# Shield_Schematic.net
KiCad netlist of a schematic drawn in EAGLE
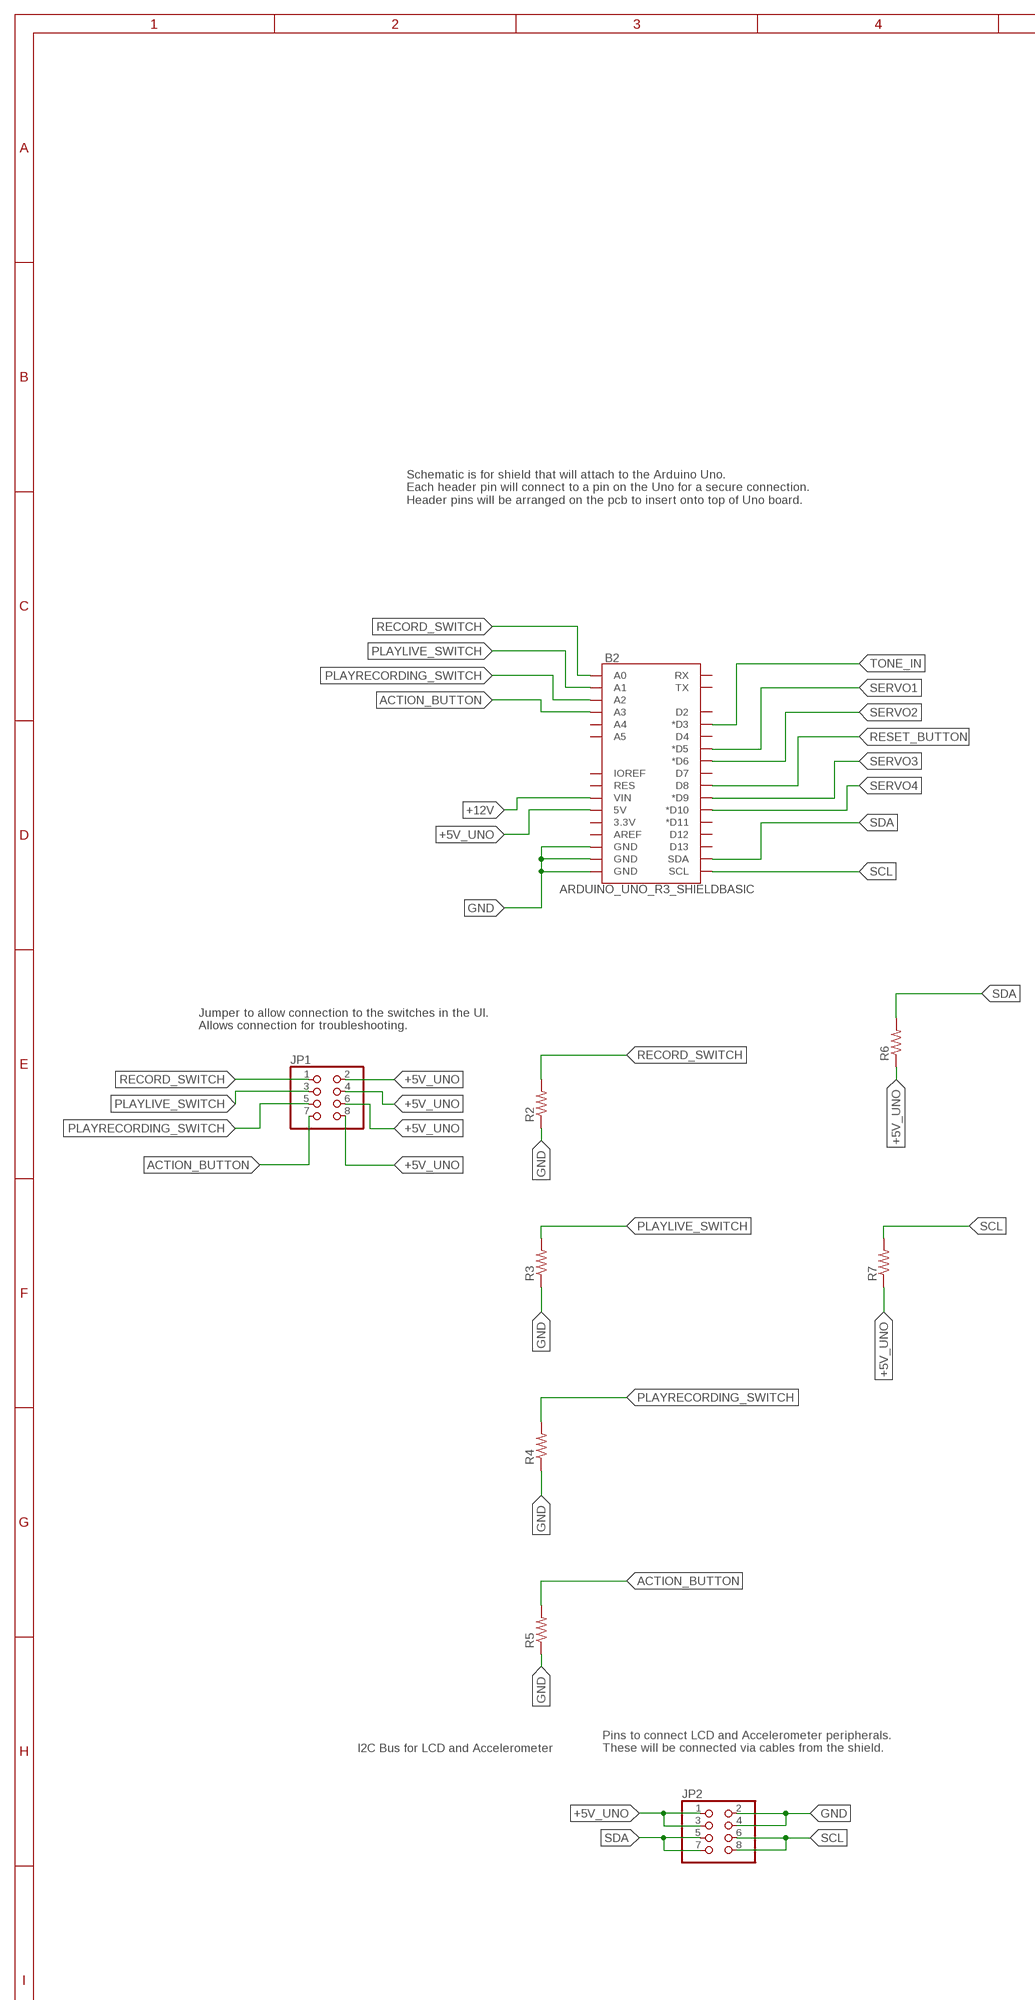
[diagram p0: schematic, sheet 1, part 1 of 2]
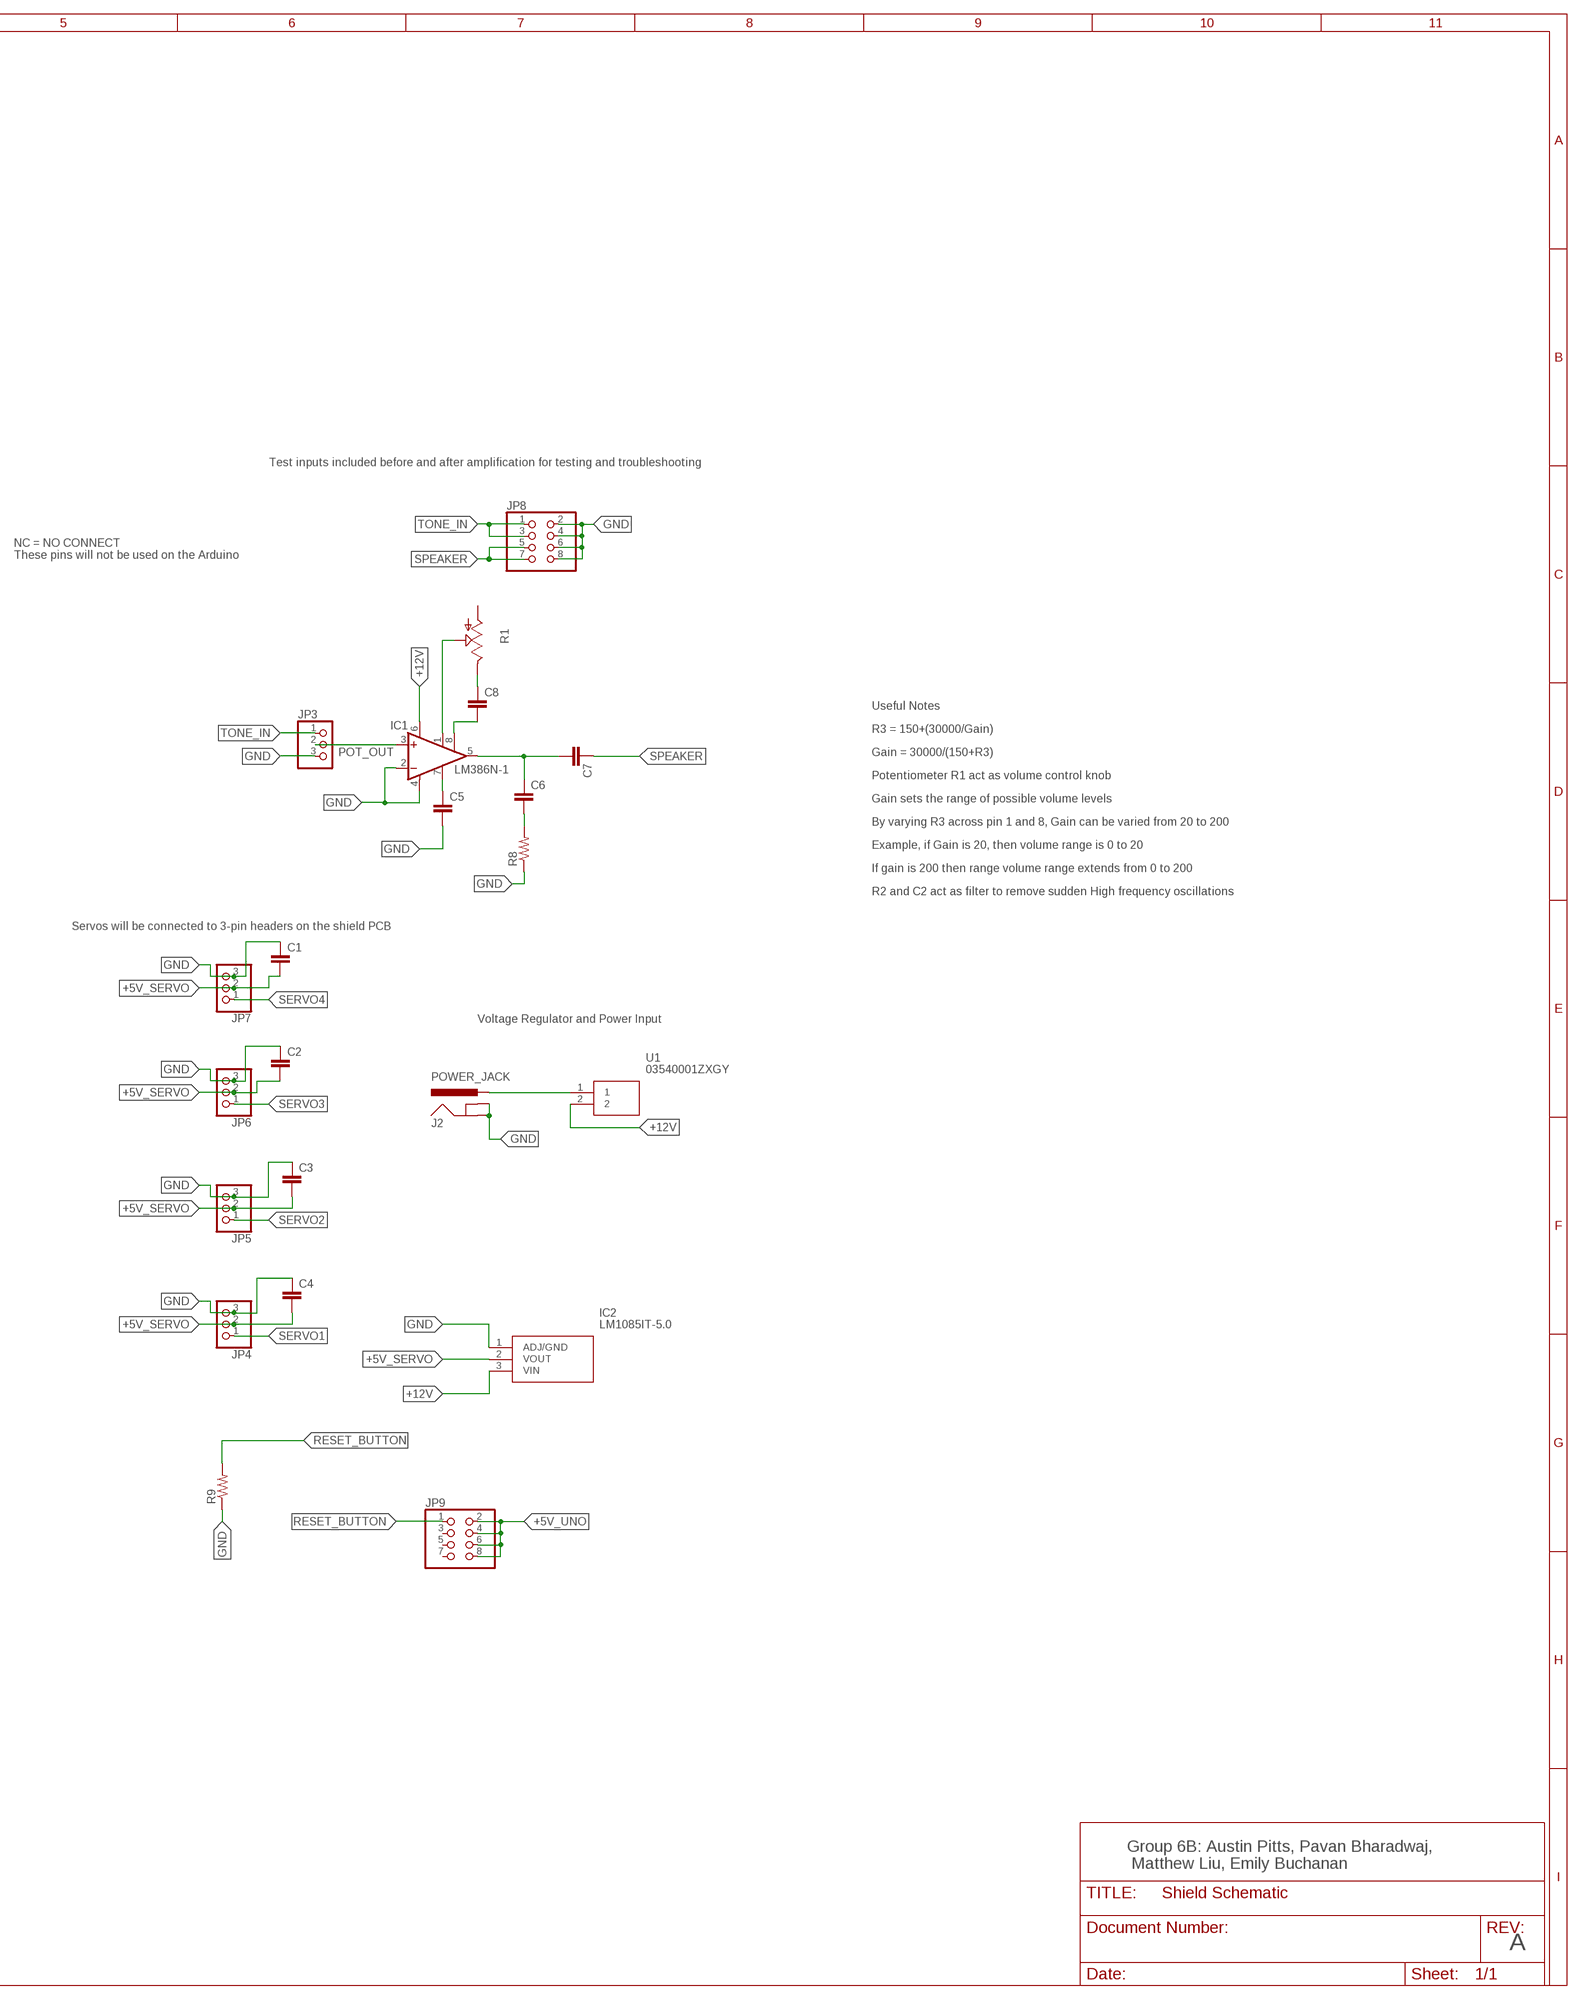
[diagram p1: schematic, sheet 1, part 2 of 2]

(export (version "E")
  (design (tool "Eeschema 10.0.6"))
  (components
    (comp (ref "B2")
      (value "ARDUINO_UNO_R3_SHIELDBASIC")
      (footprint "eagle-import:UNO_R3_SHIELD")
      (libsource (lib "eagle-import") (part "ARDUINO_UNO_R3_SHIELDBASIC"))
    )
    (comp (ref "C1")
      (value "C2,5-3")
      (footprint "eagle-import:C2.5-3")
      (libsource (lib "eagle-import") (part "C2,5-3"))
    )
    (comp (ref "C2")
      (value "C2,5-3")
      (footprint "eagle-import:C2.5-3")
      (libsource (lib "eagle-import") (part "C2,5-3"))
    )
    (comp (ref "C3")
      (value "C2,5-3")
      (footprint "eagle-import:C2.5-3")
      (libsource (lib "eagle-import") (part "C2,5-3"))
    )
    (comp (ref "C4")
      (value "C2,5-3")
      (footprint "eagle-import:C2.5-3")
      (libsource (lib "eagle-import") (part "C2,5-3"))
    )
    (comp (ref "C5")
      (value "C2,5-3")
      (footprint "eagle-import:C2.5-3")
      (libsource (lib "eagle-import") (part "C2,5-3"))
    )
    (comp (ref "C6")
      (value "C2,5-3")
      (footprint "eagle-import:C2.5-3")
      (libsource (lib "eagle-import") (part "C2,5-3"))
    )
    (comp (ref "C7")
      (value "C2,5-3")
      (footprint "eagle-import:C2.5-3")
      (libsource (lib "eagle-import") (part "C2,5-3"))
    )
    (comp (ref "C8")
      (value "C2,5-3")
      (footprint "eagle-import:C2.5-3")
      (libsource (lib "eagle-import") (part "C2,5-3"))
    )
    (comp (ref "IC1")
      (value "LM386N-1")
      (footprint "eagle-import:DIL08")
      (libsource (lib "eagle-import") (part "LM386?-N1"))
    )
    (comp (ref "IC2")
      (value "LM1085IT-5.0")
      (footprint "eagle-import:TO254P470X1016X2222-3P")
      (fields (field (name "MOUSER_PART_NUMBER") "926-LM1085IT-50"))
      (libsource (lib "eagle-import") (part "LM1085IT-5.0"))
    )
    (comp (ref "J2")
      (value "POWER_JACK")
      (footprint "eagle-import:POWER_JACK_PTH")
      (libsource (lib "eagle-import") (part "POWER_JACK"))
    )
    (comp (ref "JP1")
      (value "PINHD-2X4")
      (footprint "eagle-import:2X04")
      (libsource (lib "eagle-import") (part "PINHD-2X4"))
    )
    (comp (ref "JP2")
      (value "PINHD-2X4")
      (footprint "eagle-import:2X04")
      (libsource (lib "eagle-import") (part "PINHD-2X4"))
    )
    (comp (ref "JP3")
      (value "PINHD-1X3")
      (footprint "eagle-import:1X03")
      (libsource (lib "eagle-import") (part "PINHD-1X3"))
    )
    (comp (ref "JP4")
      (value "PINHD-1X3")
      (footprint "eagle-import:1X03")
      (libsource (lib "eagle-import") (part "adafruit_420_PINHD-1X3"))
    )
    (comp (ref "JP5")
      (value "PINHD-1X3")
      (footprint "eagle-import:1X03")
      (libsource (lib "eagle-import") (part "adafruit_420_PINHD-1X3"))
    )
    (comp (ref "JP6")
      (value "PINHD-1X3")
      (footprint "eagle-import:1X03")
      (libsource (lib "eagle-import") (part "adafruit_420_PINHD-1X3"))
    )
    (comp (ref "JP7")
      (value "PINHD-1X3")
      (footprint "eagle-import:1X03")
      (libsource (lib "eagle-import") (part "adafruit_420_PINHD-1X3"))
    )
    (comp (ref "JP8")
      (value "PINHD-2X4")
      (footprint "eagle-import:2X04")
      (libsource (lib "eagle-import") (part "PINHD-2X4"))
    )
    (comp (ref "JP9")
      (value "PINHD-2X4")
      (footprint "eagle-import:2X04")
      (libsource (lib "eagle-import") (part "PINHD-2X4"))
    )
    (comp (ref "R1")
      (value "TRIM_US-B25P")
      (footprint "eagle-import:B25P")
      (libsource (lib "eagle-import") (part "TRIM_US-B25P"))
    )
    (comp (ref "R2")
      (value "R-US_0207/7")
      (footprint "eagle-import:0207_7")
      (libsource (lib "eagle-import") (part "R-US_0207/7"))
    )
    (comp (ref "R3")
      (value "R-US_0207/7")
      (footprint "eagle-import:0207_7")
      (libsource (lib "eagle-import") (part "R-US_0207/7"))
    )
    (comp (ref "R4")
      (value "R-US_0207/7")
      (footprint "eagle-import:0207_7")
      (libsource (lib "eagle-import") (part "R-US_0207/7"))
    )
    (comp (ref "R5")
      (value "R-US_0207/7")
      (footprint "eagle-import:0207_7")
      (libsource (lib "eagle-import") (part "R-US_0207/7"))
    )
    (comp (ref "R6")
      (value "R-US_0207/7")
      (footprint "eagle-import:0207_7")
      (libsource (lib "eagle-import") (part "R-US_0207/7"))
    )
    (comp (ref "R7")
      (value "R-US_0207/7")
      (footprint "eagle-import:0207_7")
      (libsource (lib "eagle-import") (part "R-US_0207/7"))
    )
    (comp (ref "R8")
      (value "R-US_0207/7")
      (footprint "eagle-import:0207_7")
      (libsource (lib "eagle-import") (part "R-US_0207/7"))
    )
    (comp (ref "R9")
      (value "R-US_0207/7")
      (footprint "eagle-import:0207_7")
      (libsource (lib "eagle-import") (part "R-US_0207/7"))
    )
    (comp (ref "U1")
      (value "03540001ZXGY")
      (footprint "eagle-import:03540101ZXGY")
      (fields (field (name "MOUSER_PART_NUMBER") "576-03540001ZXGY"))
      (libsource (lib "eagle-import") (part "03540001ZXGY"))
    )
  )
  (nets
    (net (code "1") (name "+5V_SERVO") (class "Default")
      (node (ref "C1") (pin "2") (pinfunction "2_2") (pintype "passive"))
      (node (ref "C2") (pin "2") (pinfunction "2_2") (pintype "passive"))
      (node (ref "C3") (pin "2") (pinfunction "2_2") (pintype "passive"))
      (node (ref "C4") (pin "2") (pinfunction "2_2") (pintype "passive"))
      (node (ref "IC2") (pin "2") (pinfunction "VOUT_2") (pintype "bidirectional"))
      (node (ref "JP4") (pin "2") (pinfunction "2_2") (pintype "passive"))
      (node (ref "JP5") (pin "2") (pinfunction "2_2") (pintype "passive"))
      (node (ref "JP6") (pin "2") (pinfunction "2_2") (pintype "passive"))
      (node (ref "JP7") (pin "2") (pinfunction "2_2") (pintype "passive"))
    )
    (net (code "2") (name "+5V_UNO") (class "Default")
      (node (ref "B2") (pin "5V") (pinfunction "5V_5V") (pintype "bidirectional"))
      (node (ref "JP1") (pin "2") (pinfunction "2_2") (pintype "passive"))
      (node (ref "JP1") (pin "4") (pinfunction "4_4") (pintype "passive"))
      (node (ref "JP1") (pin "6") (pinfunction "6_6") (pintype "passive"))
      (node (ref "JP1") (pin "8") (pinfunction "8_8") (pintype "passive"))
      (node (ref "JP2") (pin "1") (pinfunction "1_1") (pintype "passive"))
      (node (ref "JP2") (pin "3") (pinfunction "3_3") (pintype "passive"))
      (node (ref "JP9") (pin "2") (pinfunction "2_2") (pintype "passive"))
      (node (ref "JP9") (pin "4") (pinfunction "4_4") (pintype "passive"))
      (node (ref "JP9") (pin "6") (pinfunction "6_6") (pintype "passive"))
      (node (ref "JP9") (pin "8") (pinfunction "8_8") (pintype "passive"))
      (node (ref "R6") (pin "1") (pinfunction "1_1") (pintype "passive"))
      (node (ref "R7") (pin "1") (pinfunction "1_1") (pintype "passive"))
    )
    (net (code "3") (name "+12V") (class "Default")
      (node (ref "B2") (pin "VIN") (pinfunction "VIN_VIN") (pintype "bidirectional"))
      (node (ref "IC1") (pin "6") (pinfunction "VS_6") (pintype "power_in"))
      (node (ref "IC2") (pin "3") (pinfunction "VIN_3") (pintype "bidirectional"))
      (node (ref "U1") (pin "2") (pinfunction "2_2") (pintype "bidirectional"))
    )
    (net (code "4") (name "/POT_OUT") (class "Default")
      (node (ref "IC1") (pin "3") (pinfunction "+IN_3") (pintype "input"))
      (node (ref "JP3") (pin "2") (pinfunction "2_2") (pintype "passive"))
    )
    (net (code "5") (name "ACTION_BUTTON") (class "Default")
      (node (ref "B2") (pin "A3") (pinfunction "A3_A3") (pintype "bidirectional"))
      (node (ref "JP1") (pin "7") (pinfunction "7_7") (pintype "passive"))
      (node (ref "R5") (pin "2") (pinfunction "2_2") (pintype "passive"))
    )
    (net (code "6") (name "GND") (class "Default")
      (node (ref "B2") (pin "GND@0") (pinfunction "GND_GND@0") (pintype "bidirectional"))
      (node (ref "B2") (pin "GND@1") (pinfunction "GND_GND@1") (pintype "bidirectional"))
      (node (ref "B2") (pin "GND@2") (pinfunction "GND_GND@2") (pintype "bidirectional"))
      (node (ref "C1") (pin "1") (pinfunction "1_1") (pintype "passive"))
      (node (ref "C2") (pin "1") (pinfunction "1_1") (pintype "passive"))
      (node (ref "C3") (pin "1") (pinfunction "1_1") (pintype "passive"))
      (node (ref "C4") (pin "1") (pinfunction "1_1") (pintype "passive"))
      (node (ref "C5") (pin "2") (pinfunction "2_2") (pintype "passive"))
      (node (ref "IC1") (pin "2") (pinfunction "-IN_2") (pintype "input"))
      (node (ref "IC1") (pin "4") (pinfunction "GND_4") (pintype "power_in"))
      (node (ref "IC2") (pin "1") (pinfunction "ADJ/GND_1") (pintype "bidirectional"))
      (node (ref "J2") (pin "GND") (pinfunction "GND_GND") (pintype "bidirectional"))
      (node (ref "J2") (pin "GNDBREAK") (pinfunction "GNDBREAK_GNDBREAK") (pintype "bidirectional"))
      (node (ref "JP2") (pin "2") (pinfunction "2_2") (pintype "passive"))
      (node (ref "JP2") (pin "4") (pinfunction "4_4") (pintype "passive"))
      (node (ref "JP3") (pin "3") (pinfunction "3_3") (pintype "passive"))
      (node (ref "JP4") (pin "3") (pinfunction "3_3") (pintype "passive"))
      (node (ref "JP5") (pin "3") (pinfunction "3_3") (pintype "passive"))
      (node (ref "JP6") (pin "3") (pinfunction "3_3") (pintype "passive"))
      (node (ref "JP7") (pin "3") (pinfunction "3_3") (pintype "passive"))
      (node (ref "JP8") (pin "2") (pinfunction "2_2") (pintype "passive"))
      (node (ref "JP8") (pin "4") (pinfunction "4_4") (pintype "passive"))
      (node (ref "JP8") (pin "6") (pinfunction "6_6") (pintype "passive"))
      (node (ref "JP8") (pin "8") (pinfunction "8_8") (pintype "passive"))
      (node (ref "R2") (pin "1") (pinfunction "1_1") (pintype "passive"))
      (node (ref "R3") (pin "1") (pinfunction "1_1") (pintype "passive"))
      (node (ref "R4") (pin "1") (pinfunction "1_1") (pintype "passive"))
      (node (ref "R5") (pin "1") (pinfunction "1_1") (pintype "passive"))
      (node (ref "R8") (pin "1") (pinfunction "1_1") (pintype "passive"))
      (node (ref "R9") (pin "1") (pinfunction "1_1") (pintype "passive"))
    )
    (net (code "7") (name "Net-(C6-Pad2)") (class "Default")
      (node (ref "C6") (pin "2") (pinfunction "2_2") (pintype "passive"))
      (node (ref "R8") (pin "2") (pinfunction "2_2") (pintype "passive"))
    )
    (net (code "8") (name "Net-(C8-Pad1)") (class "Default")
      (node (ref "C8") (pin "1") (pinfunction "1_1") (pintype "passive"))
      (node (ref "R1") (pin "E") (pinfunction "E_E") (pintype "passive"))
    )
    (net (code "9") (name "Net-(C8-Pad2)") (class "Default")
      (node (ref "C8") (pin "2") (pinfunction "2_2") (pintype "passive"))
      (node (ref "IC1") (pin "8") (pinfunction "GAIN_8") (pintype "passive"))
    )
    (net (code "10") (name "Net-(IC1-BYPASS)") (class "Default")
      (node (ref "C5") (pin "1") (pinfunction "1_1") (pintype "passive"))
      (node (ref "IC1") (pin "7") (pinfunction "BYPASS_7") (pintype "passive"))
    )
    (net (code "11") (name "Net-(IC1-GAIN-Pad1)") (class "Default")
      (node (ref "IC1") (pin "1") (pinfunction "GAIN_1") (pintype "passive"))
      (node (ref "R1") (pin "S") (pinfunction "S_S") (pintype "passive"))
    )
    (net (code "12") (name "Net-(IC1-OUT)") (class "Default")
      (node (ref "C6") (pin "1") (pinfunction "1_1") (pintype "passive"))
      (node (ref "C7") (pin "2") (pinfunction "2_2") (pintype "passive"))
      (node (ref "IC1") (pin "5") (pinfunction "OUT_5") (pintype "output"))
    )
    (net (code "13") (name "Net-(J2-PadPWR)") (class "Default")
      (node (ref "J2") (pin "PWR") (pinfunction "PWR_PWR") (pintype "bidirectional"))
      (node (ref "U1") (pin "1") (pinfunction "1_1") (pintype "bidirectional"))
    )
    (net (code "14") (name "PLAYLIVE_SWITCH") (class "Default")
      (node (ref "B2") (pin "A1") (pinfunction "A1_A1") (pintype "bidirectional"))
      (node (ref "JP1") (pin "3") (pinfunction "3_3") (pintype "passive"))
      (node (ref "R3") (pin "2") (pinfunction "2_2") (pintype "passive"))
    )
    (net (code "15") (name "PLAYRECORDING_SWITCH") (class "Default")
      (node (ref "B2") (pin "A2") (pinfunction "A2_A2") (pintype "bidirectional"))
      (node (ref "JP1") (pin "5") (pinfunction "5_5") (pintype "passive"))
      (node (ref "R4") (pin "2") (pinfunction "2_2") (pintype "passive"))
    )
    (net (code "16") (name "RECORD_SWITCH") (class "Default")
      (node (ref "B2") (pin "A0") (pinfunction "A0_A0") (pintype "bidirectional"))
      (node (ref "JP1") (pin "1") (pinfunction "1_1") (pintype "passive"))
      (node (ref "R2") (pin "2") (pinfunction "2_2") (pintype "passive"))
    )
    (net (code "17") (name "RESET_BUTTON") (class "Default")
      (node (ref "B2") (pin "D8") (pinfunction "D8_D8") (pintype "bidirectional"))
      (node (ref "JP9") (pin "1") (pinfunction "1_1") (pintype "passive"))
      (node (ref "R9") (pin "2") (pinfunction "2_2") (pintype "passive"))
    )
    (net (code "18") (name "SCL") (class "Default")
      (node (ref "B2") (pin "SCL") (pinfunction "SCL_SCL") (pintype "bidirectional"))
      (node (ref "JP2") (pin "6") (pinfunction "6_6") (pintype "passive"))
      (node (ref "JP2") (pin "8") (pinfunction "8_8") (pintype "passive"))
      (node (ref "R7") (pin "2") (pinfunction "2_2") (pintype "passive"))
    )
    (net (code "19") (name "SDA") (class "Default")
      (node (ref "B2") (pin "SDA") (pinfunction "SDA_SDA") (pintype "bidirectional"))
      (node (ref "JP2") (pin "5") (pinfunction "5_5") (pintype "passive"))
      (node (ref "JP2") (pin "7") (pinfunction "7_7") (pintype "passive"))
      (node (ref "R6") (pin "2") (pinfunction "2_2") (pintype "passive"))
    )
    (net (code "20") (name "SERVO1") (class "Default")
      (node (ref "B2") (pin "D5") (pinfunction "*D5_D5") (pintype "bidirectional"))
      (node (ref "JP4") (pin "1") (pinfunction "1_1") (pintype "passive"))
    )
    (net (code "21") (name "SERVO2") (class "Default")
      (node (ref "B2") (pin "D6") (pinfunction "*D6_D6") (pintype "bidirectional"))
      (node (ref "JP5") (pin "1") (pinfunction "1_1") (pintype "passive"))
    )
    (net (code "22") (name "SERVO3") (class "Default")
      (node (ref "B2") (pin "D9") (pinfunction "*D9_D9") (pintype "bidirectional"))
      (node (ref "JP6") (pin "1") (pinfunction "1_1") (pintype "passive"))
    )
    (net (code "23") (name "SERVO4") (class "Default")
      (node (ref "B2") (pin "D10") (pinfunction "*D10_D10") (pintype "bidirectional"))
      (node (ref "JP7") (pin "1") (pinfunction "1_1") (pintype "passive"))
    )
    (net (code "24") (name "SPEAKER") (class "Default")
      (node (ref "C7") (pin "1") (pinfunction "1_1") (pintype "passive"))
      (node (ref "JP8") (pin "5") (pinfunction "5_5") (pintype "passive"))
      (node (ref "JP8") (pin "7") (pinfunction "7_7") (pintype "passive"))
    )
    (net (code "25") (name "TONE_IN") (class "Default")
      (node (ref "B2") (pin "D3") (pinfunction "*D3_D3") (pintype "bidirectional"))
      (node (ref "JP3") (pin "1") (pinfunction "1_1") (pintype "passive"))
      (node (ref "JP8") (pin "1") (pinfunction "1_1") (pintype "passive"))
      (node (ref "JP8") (pin "3") (pinfunction "3_3") (pintype "passive"))
    )
    (net (code "26") (name "unconnected-(B2-*D11-PadD11)") (class "Default")
      (node (ref "B2") (pin "D11") (pinfunction "*D11_D11") (pintype "bidirectional"))
    )
    (net (code "27") (name "unconnected-(B2-Pad3.3V)") (class "Default")
      (node (ref "B2") (pin "3.3V") (pinfunction "3.3V_3.3V") (pintype "bidirectional"))
    )
    (net (code "28") (name "unconnected-(B2-PadA4)") (class "Default")
      (node (ref "B2") (pin "A4") (pinfunction "A4_A4") (pintype "bidirectional"))
    )
    (net (code "29") (name "unconnected-(B2-PadA5)") (class "Default")
      (node (ref "B2") (pin "A5") (pinfunction "A5_A5") (pintype "bidirectional"))
    )
    (net (code "30") (name "unconnected-(B2-PadAREF)") (class "Default")
      (node (ref "B2") (pin "AREF") (pinfunction "AREF_AREF") (pintype "bidirectional"))
    )
    (net (code "31") (name "unconnected-(B2-PadD2)") (class "Default")
      (node (ref "B2") (pin "D2") (pinfunction "D2_D2") (pintype "bidirectional"))
    )
    (net (code "32") (name "unconnected-(B2-PadD4)") (class "Default")
      (node (ref "B2") (pin "D4") (pinfunction "D4_D4") (pintype "bidirectional"))
    )
    (net (code "33") (name "unconnected-(B2-PadD7)") (class "Default")
      (node (ref "B2") (pin "D7") (pinfunction "D7_D7") (pintype "bidirectional"))
    )
    (net (code "34") (name "unconnected-(B2-PadD12)") (class "Default")
      (node (ref "B2") (pin "D12") (pinfunction "D12_D12") (pintype "bidirectional"))
    )
    (net (code "35") (name "unconnected-(B2-PadD13)") (class "Default")
      (node (ref "B2") (pin "D13") (pinfunction "D13_D13") (pintype "bidirectional"))
    )
    (net (code "36") (name "unconnected-(B2-PadIOREF)") (class "Default")
      (node (ref "B2") (pin "IOREF") (pinfunction "IOREF_IOREF") (pintype "bidirectional"))
    )
    (net (code "37") (name "unconnected-(B2-PadRES)") (class "Default")
      (node (ref "B2") (pin "RES") (pinfunction "RES_RES") (pintype "bidirectional"))
    )
    (net (code "38") (name "unconnected-(B2-PadRX)") (class "Default")
      (node (ref "B2") (pin "RX") (pinfunction "RX_RX") (pintype "bidirectional"))
    )
    (net (code "39") (name "unconnected-(B2-PadTX)") (class "Default")
      (node (ref "B2") (pin "TX") (pinfunction "TX_TX") (pintype "bidirectional"))
    )
    (net (code "40") (name "unconnected-(JP9-Pad3)") (class "Default")
      (node (ref "JP9") (pin "3") (pinfunction "3_3") (pintype "passive"))
    )
    (net (code "41") (name "unconnected-(JP9-Pad5)") (class "Default")
      (node (ref "JP9") (pin "5") (pinfunction "5_5") (pintype "passive"))
    )
    (net (code "42") (name "unconnected-(JP9-Pad7)") (class "Default")
      (node (ref "JP9") (pin "7") (pinfunction "7_7") (pintype "passive"))
    )
    (net (code "43") (name "unconnected-(R1-PadA)") (class "Default")
      (node (ref "R1") (pin "A") (pinfunction "A_A") (pintype "passive"))
    )
  )
)
